# Blinker.net
KiCad netlist of a schematic drawn in EAGLE
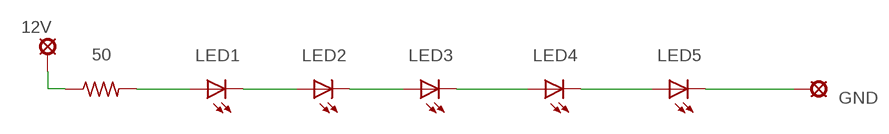
[diagram p0: schematic, sheet 1]

(export (version "E")
  (design (tool "Eeschema 10.0.6"))
  (components
    (comp (ref "12V")
      (value "LSP13")
      (footprint "eagle-import:LSP13")
      (libsource (lib "eagle-import") (part "LSP13"))
    )
    (comp (ref "50")
      (value "RESISTORSMD1206")
      (footprint "eagle-import:R1206")
      (libsource (lib "eagle-import") (part "RESISTORSMD1206"))
    )
    (comp (ref "GND")
      (value "LSP13")
      (footprint "eagle-import:LSP13")
      (libsource (lib "eagle-import") (part "LSP13"))
    )
    (comp (ref "LED1")
      (value "LED1")
      (footprint "eagle-import:CP41B")
      (libsource (lib "eagle-import") (part "LED-2AC-CP41B-WES"))
    )
    (comp (ref "LED2")
      (value "LED2")
      (footprint "eagle-import:CP41B")
      (libsource (lib "eagle-import") (part "LED-2AC-CP41B-WES"))
    )
    (comp (ref "LED3")
      (value "LED3")
      (footprint "eagle-import:CP41B")
      (libsource (lib "eagle-import") (part "LED-2AC-CP41B-WES"))
    )
    (comp (ref "LED4")
      (value "LED4")
      (footprint "eagle-import:CP41B")
      (libsource (lib "eagle-import") (part "LED-2AC-CP41B-WES"))
    )
    (comp (ref "LED5")
      (value "LED5")
      (footprint "eagle-import:CP41B")
      (libsource (lib "eagle-import") (part "LED-2AC-CP41B-WES"))
    )
  )
  (nets
    (net (code "1") (name "Net-(12V-PadMP)") (class "Default")
      (node (ref "12V") (pin "MP") (pinfunction "MP_MP") (pintype "passive"))
      (node (ref "50") (pin "1") (pinfunction "1_1") (pintype "passive"))
    )
    (net (code "2") (name "Net-(50-Pad2)") (class "Default")
      (node (ref "50") (pin "2") (pinfunction "2_2") (pintype "passive"))
      (node (ref "LED1") (pin "2") (pinfunction "A_2") (pintype "passive"))
      (node (ref "LED1") (pin "3") (pinfunction "A_3") (pintype "passive"))
    )
    (net (code "3") (name "Net-(GND-PadMP)") (class "Default")
      (node (ref "GND") (pin "MP") (pinfunction "MP_MP") (pintype "passive"))
      (node (ref "LED5") (pin "1") (pinfunction "C_1") (pintype "passive"))
      (node (ref "LED5") (pin "4") (pinfunction "C_4") (pintype "passive"))
    )
    (net (code "4") (name "Net-(LED1-C-Pad1)") (class "Default")
      (node (ref "LED1") (pin "1") (pinfunction "C_1") (pintype "passive"))
      (node (ref "LED1") (pin "4") (pinfunction "C_4") (pintype "passive"))
      (node (ref "LED2") (pin "2") (pinfunction "A_2") (pintype "passive"))
      (node (ref "LED2") (pin "3") (pinfunction "A_3") (pintype "passive"))
    )
    (net (code "5") (name "Net-(LED2-C-Pad1)") (class "Default")
      (node (ref "LED2") (pin "1") (pinfunction "C_1") (pintype "passive"))
      (node (ref "LED2") (pin "4") (pinfunction "C_4") (pintype "passive"))
      (node (ref "LED3") (pin "2") (pinfunction "A_2") (pintype "passive"))
      (node (ref "LED3") (pin "3") (pinfunction "A_3") (pintype "passive"))
    )
    (net (code "6") (name "Net-(LED3-C-Pad1)") (class "Default")
      (node (ref "LED3") (pin "1") (pinfunction "C_1") (pintype "passive"))
      (node (ref "LED3") (pin "4") (pinfunction "C_4") (pintype "passive"))
      (node (ref "LED4") (pin "2") (pinfunction "A_2") (pintype "passive"))
      (node (ref "LED4") (pin "3") (pinfunction "A_3") (pintype "passive"))
    )
    (net (code "7") (name "Net-(LED4-C-Pad1)") (class "Default")
      (node (ref "LED4") (pin "1") (pinfunction "C_1") (pintype "passive"))
      (node (ref "LED4") (pin "4") (pinfunction "C_4") (pintype "passive"))
      (node (ref "LED5") (pin "2") (pinfunction "A_2") (pintype "passive"))
      (node (ref "LED5") (pin "3") (pinfunction "A_3") (pintype "passive"))
    )
  )
)
